# Qwiic_Spectral_Sensor-AS7265x.net
KiCad netlist of a schematic drawn in EAGLE
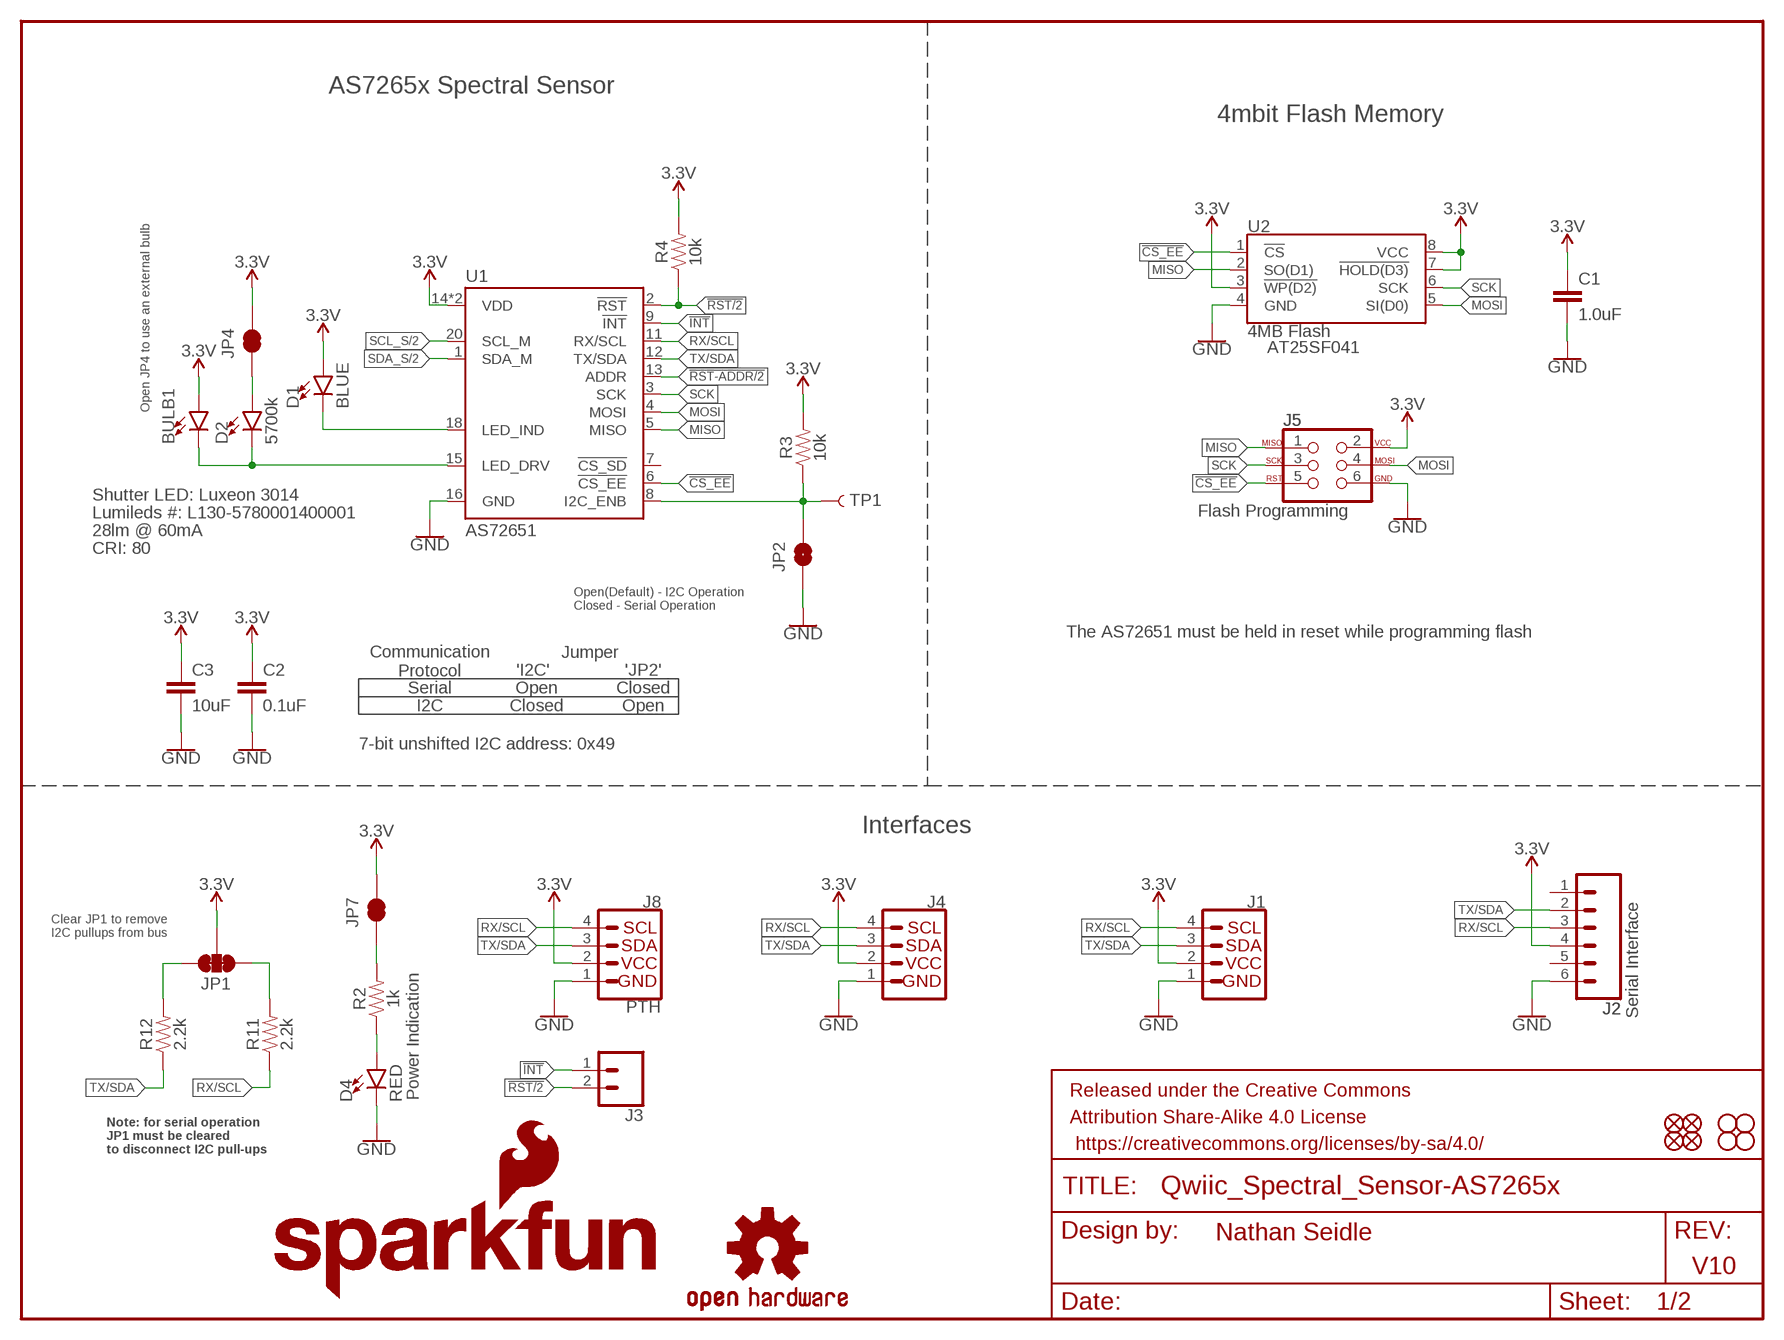
[diagram p0: schematic, sheet 1]
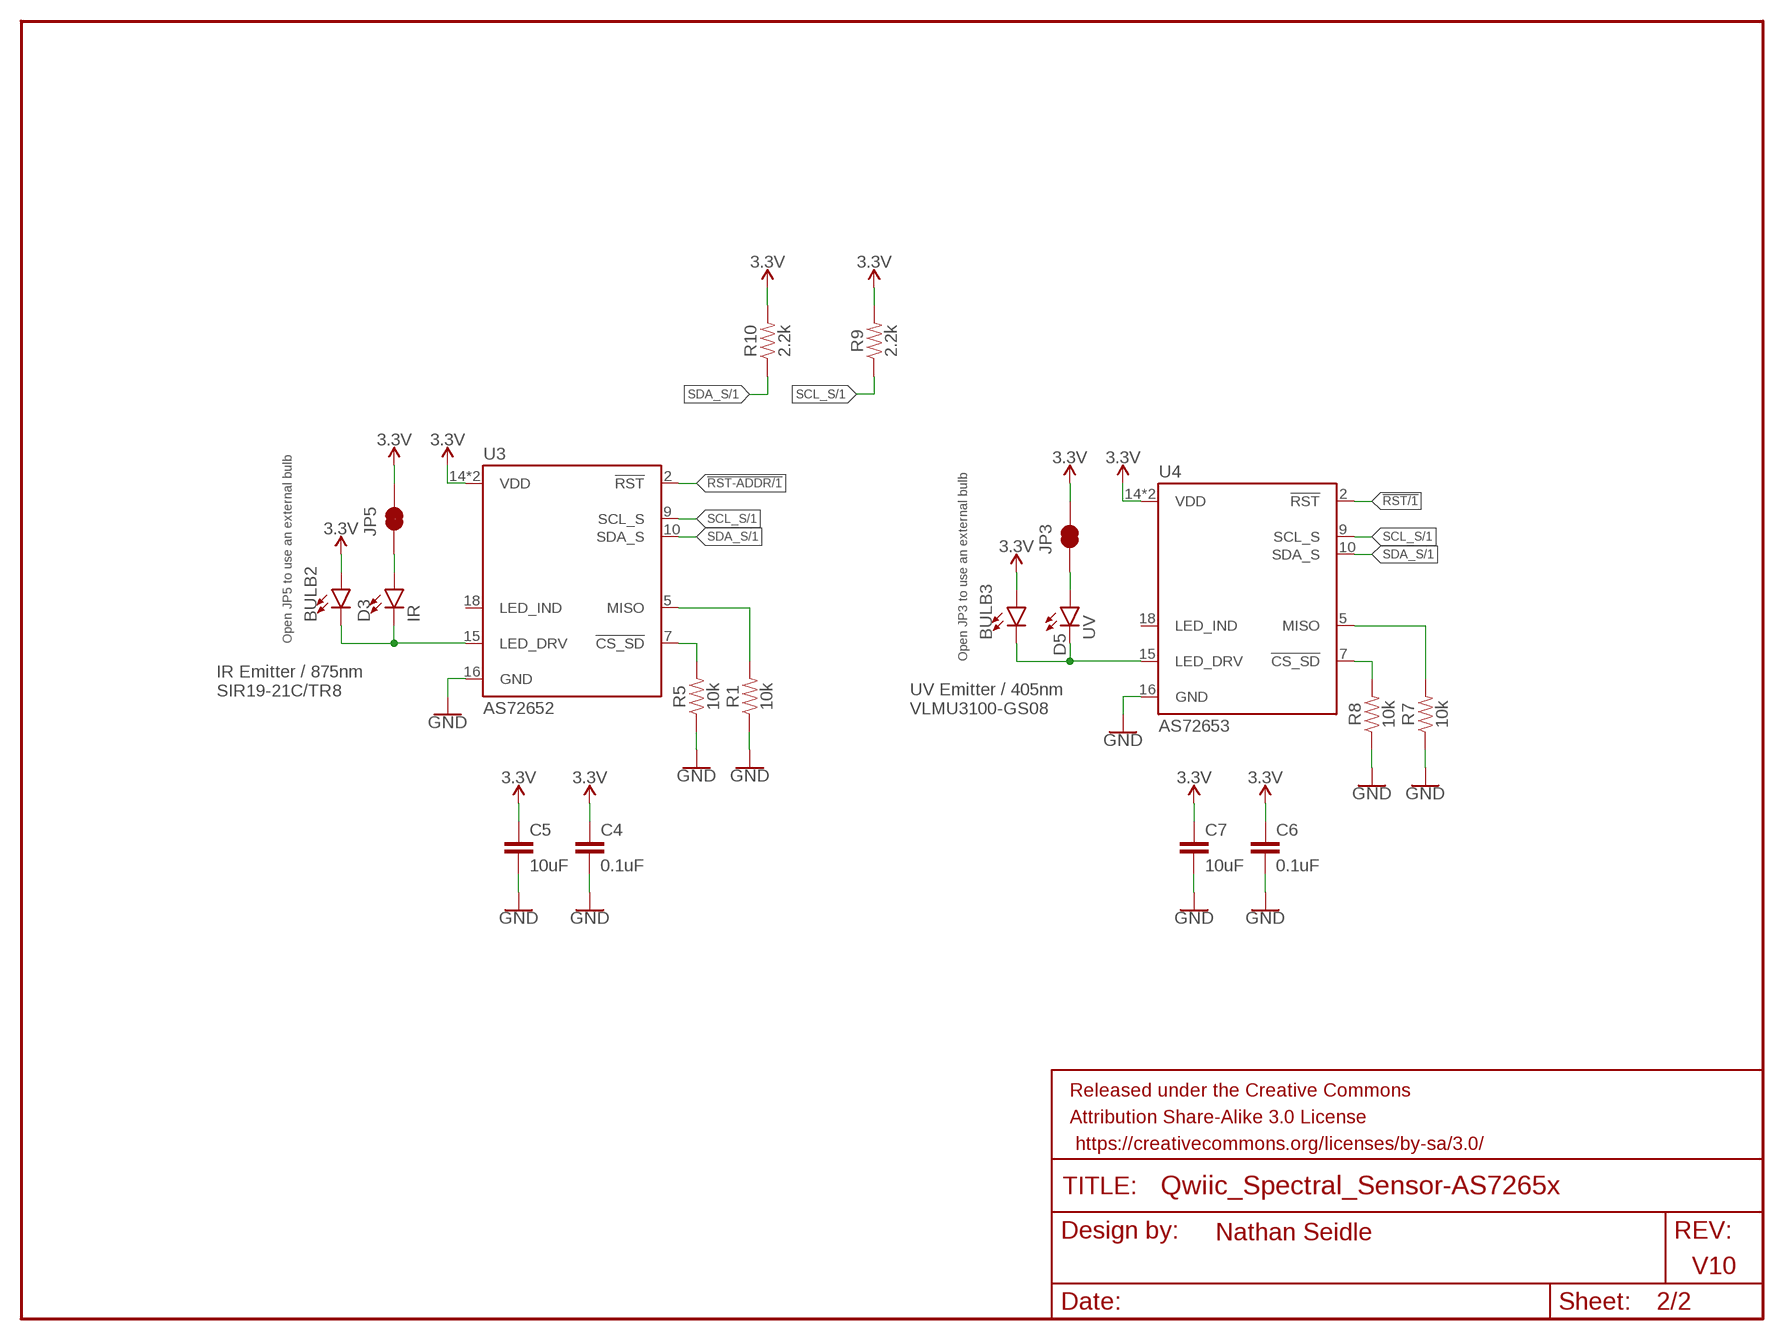
[diagram p1: schematic, sheet 2]

(export (version "E")
  (design (tool "Eeschema 10.0.6"))
  (components
    (comp (ref "BULB2")
      (value "LEDNS")
      (footprint "eagle-import:LED_5MM_NOSILK")
      (libsource (lib "eagle-import") (part "LEDNS"))
    )
    (comp (ref "BULB3")
      (value "LEDNS")
      (footprint "eagle-import:LED_5MM_NOSILK")
      (libsource (lib "eagle-import") (part "LEDNS"))
    )
    (comp (ref "C4")
      (value "0.1uF")
      (footprint "eagle-import:0603")
      (libsource (lib "eagle-import") (part "0.1UF-0603-25V-(+80/-20%)"))
    )
    (comp (ref "C5")
      (value "10uF")
      (footprint "eagle-import:0603")
      (libsource (lib "eagle-import") (part "10UF-0603-6.3V-20%"))
    )
    (comp (ref "C6")
      (value "0.1uF")
      (footprint "eagle-import:0603")
      (libsource (lib "eagle-import") (part "0.1UF-0603-25V-(+80/-20%)"))
    )
    (comp (ref "C7")
      (value "10uF")
      (footprint "eagle-import:0603")
      (libsource (lib "eagle-import") (part "10UF-0603-6.3V-20%"))
    )
    (comp (ref "D3")
      (value "IR")
      (footprint "eagle-import:LED-0603")
      (libsource (lib "eagle-import") (part "LED-IR0603"))
    )
    (comp (ref "D5")
      (value "UV")
      (footprint "eagle-import:PLCC-2")
      (libsource (lib "eagle-import") (part "LED-UVPLCC"))
    )
    (comp (ref "FRAME3")
      (value "FRAME-LETTER")
      (footprint "eagle-import:CREATIVE_COMMONS")
      (libsource (lib "eagle-import") (part "SparkFun-Retired_FRAME-LETTER"))
    )
    (comp (ref "JP3")
      (value "JUMPER-SMT_2_NC_TRACE_NO-SILK")
      (footprint "eagle-import:SMT-JUMPER_2_NC_TRACE_NO-SILK")
      (libsource (lib "eagle-import") (part "JUMPER-SMT_2_NC_TRACE_NO-SILK"))
    )
    (comp (ref "JP5")
      (value "JUMPER-SMT_2_NC_TRACE_NO-SILK")
      (footprint "eagle-import:SMT-JUMPER_2_NC_TRACE_NO-SILK")
      (libsource (lib "eagle-import") (part "JUMPER-SMT_2_NC_TRACE_NO-SILK"))
    )
    (comp (ref "R1")
      (value "10k")
      (footprint "eagle-import:0603")
      (libsource (lib "eagle-import") (part "10KOHM-0603-1/10W-1%"))
    )
    (comp (ref "R5")
      (value "10k")
      (footprint "eagle-import:0603")
      (libsource (lib "eagle-import") (part "10KOHM-0603-1/10W-1%"))
    )
    (comp (ref "R7")
      (value "10k")
      (footprint "eagle-import:0603")
      (libsource (lib "eagle-import") (part "10KOHM-0603-1/10W-1%"))
    )
    (comp (ref "R8")
      (value "10k")
      (footprint "eagle-import:0603")
      (libsource (lib "eagle-import") (part "10KOHM-0603-1/10W-1%"))
    )
    (comp (ref "R9")
      (value "2.2k")
      (footprint "eagle-import:0603")
      (libsource (lib "eagle-import") (part "2.2KOHM-0603-1/10W-1%"))
    )
    (comp (ref "R10")
      (value "2.2k")
      (footprint "eagle-import:0603")
      (libsource (lib "eagle-import") (part "2.2KOHM-0603-1/10W-1%"))
    )
    (comp (ref "U3")
      (value "AS72652")
      (footprint "eagle-import:LGA20")
      (libsource (lib "eagle-import") (part "AS72652"))
    )
    (comp (ref "U4")
      (value "AS72653")
      (footprint "eagle-import:LGA20")
      (libsource (lib "eagle-import") (part "AS72653"))
    )
    (comp (ref "BULB1")
      (value "LEDNS")
      (footprint "eagle-import:LED_5MM_NOSILK")
      (libsource (lib "eagle-import") (part "LEDNS"))
    )
    (comp (ref "C1")
      (value "1.0uF")
      (footprint "eagle-import:0603")
      (libsource (lib "eagle-import") (part "1.0UF-0603-16V-10%"))
    )
    (comp (ref "C2")
      (value "0.1uF")
      (footprint "eagle-import:0603")
      (libsource (lib "eagle-import") (part "0.1UF-0603-25V-(+80/-20%)"))
    )
    (comp (ref "C3")
      (value "10uF")
      (footprint "eagle-import:0603")
      (libsource (lib "eagle-import") (part "10UF-0603-6.3V-20%"))
    )
    (comp (ref "D1")
      (value "BLUE")
      (footprint "eagle-import:LED-0603")
      (libsource (lib "eagle-import") (part "LED-BLUE0603"))
    )
    (comp (ref "D2")
      (value "5700k")
      (footprint "eagle-import:SUPER_BRIGHT_SMD_LED_3014")
      (libsource (lib "eagle-import") (part "LED-WHITE3014"))
    )
    (comp (ref "D4")
      (value "RED")
      (footprint "eagle-import:LED-0603")
      (libsource (lib "eagle-import") (part "LED-RED0603"))
    )
    (comp (ref "FD1")
      (value "FIDUCIAL1X2")
      (footprint "eagle-import:FIDUCIAL-1X2")
      (libsource (lib "eagle-import") (part "FIDUCIAL1X2"))
    )
    (comp (ref "FD2")
      (value "FIDUCIAL1X2")
      (footprint "eagle-import:FIDUCIAL-1X2")
      (libsource (lib "eagle-import") (part "FIDUCIAL1X2"))
    )
    (comp (ref "FD3")
      (value "FIDUCIAL1X2")
      (footprint "eagle-import:FIDUCIAL-1X2")
      (libsource (lib "eagle-import") (part "FIDUCIAL1X2"))
    )
    (comp (ref "FD4")
      (value "FIDUCIAL1X2")
      (footprint "eagle-import:FIDUCIAL-1X2")
      (libsource (lib "eagle-import") (part "FIDUCIAL1X2"))
    )
    (comp (ref "FRAME1")
      (value "FRAME-LETTER")
      (footprint "eagle-import:CREATIVE_COMMONS")
      (libsource (lib "eagle-import") (part "FRAME-LETTER"))
    )
    (comp (ref "H1")
      (value "STAND-OFF")
      (footprint "eagle-import:STAND-OFF")
      (libsource (lib "eagle-import") (part "STAND-OFF"))
    )
    (comp (ref "H2")
      (value "STAND-OFF")
      (footprint "eagle-import:STAND-OFF")
      (libsource (lib "eagle-import") (part "STAND-OFF"))
    )
    (comp (ref "H3")
      (value "STAND-OFF")
      (footprint "eagle-import:STAND-OFF")
      (libsource (lib "eagle-import") (part "STAND-OFF"))
    )
    (comp (ref "H4")
      (value "STAND-OFF")
      (footprint "eagle-import:STAND-OFF")
      (libsource (lib "eagle-import") (part "STAND-OFF"))
    )
    (comp (ref "J1")
      (value "QWIIC_CONNECTORJS-1MM")
      (footprint "eagle-import:1X04_1MM_RA")
      (libsource (lib "eagle-import") (part "QWIIC_CONNECTORJS-1MM"))
    )
    (comp (ref "J2")
      (value "Serial Interface")
      (footprint "eagle-import:1X06_NO_SILK")
      (libsource (lib "eagle-import") (part "CONN_06NO_SILK_FEMALE_PTH"))
    )
    (comp (ref "J3")
      (value "CONN_021X02_NO_SILK")
      (footprint "eagle-import:1X02_NO_SILK")
      (libsource (lib "eagle-import") (part "CONN_021X02_NO_SILK"))
    )
    (comp (ref "J4")
      (value "QWIIC_CONNECTORJS-1MM")
      (footprint "eagle-import:1X04_1MM_RA")
      (libsource (lib "eagle-import") (part "QWIIC_CONNECTORJS-1MM"))
    )
    (comp (ref "J5")
      (value "Flash Programming")
      (footprint "eagle-import:2X3_TEST_POINTS")
      (libsource (lib "eagle-import") (part "AVR_SPI_PROG_3X2TESTPOINTS"))
    )
    (comp (ref "J8")
      (value "PTH")
      (footprint "eagle-import:1X04_NO_SILK")
      (libsource (lib "eagle-import") (part "I2C_STANDARD_NO_SILK"))
    )
    (comp (ref "JP1")
      (value "JUMPER-SMT_3_2-NC_TRACE_SILK")
      (footprint "eagle-import:SMT-JUMPER_3_2-NC_TRACE_SILK")
      (libsource (lib "eagle-import") (part "JUMPER-SMT_3_2-NC_TRACE_SILK"))
    )
    (comp (ref "JP2")
      (value "JUMPER-SMT_2_NO_SILK")
      (footprint "eagle-import:SMT-JUMPER_2_NO_SILK")
      (libsource (lib "eagle-import") (part "JUMPER-SMT_2_NO_SILK"))
    )
    (comp (ref "JP4")
      (value "JUMPER-SMT_2_NC_TRACE_NO-SILK")
      (footprint "eagle-import:SMT-JUMPER_2_NC_TRACE_NO-SILK")
      (libsource (lib "eagle-import") (part "JUMPER-SMT_2_NC_TRACE_NO-SILK"))
    )
    (comp (ref "JP7")
      (value "JUMPER-SMT_2_NC_TRACE_NO-SILK")
      (footprint "eagle-import:SMT-JUMPER_2_NC_TRACE_NO-SILK")
      (libsource (lib "eagle-import") (part "JUMPER-SMT_2_NC_TRACE_NO-SILK"))
    )
    (comp (ref "LOGO1")
      (value "SFE_LOGO_NAME_FLAME.1_INCH")
      (footprint "eagle-import:SFE_LOGO_NAME_FLAME_.1")
      (libsource (lib "eagle-import") (part "SFE_LOGO_NAME_FLAME.1_INCH"))
    )
    (comp (ref "LOGO4")
      (value "OSHW-LOGOS")
      (footprint "eagle-import:OSHW-LOGO-S")
      (libsource (lib "eagle-import") (part "OSHW-LOGOS"))
    )
    (comp (ref "R2")
      (value "1k")
      (footprint "eagle-import:0603")
      (libsource (lib "eagle-import") (part "1KOHM-0603-1/10W-1%"))
    )
    (comp (ref "R3")
      (value "10k")
      (footprint "eagle-import:0603")
      (libsource (lib "eagle-import") (part "10KOHM-0603-1/10W-1%"))
    )
    (comp (ref "R4")
      (value "10k")
      (footprint "eagle-import:0603")
      (libsource (lib "eagle-import") (part "10KOHM-0603-1/10W-1%"))
    )
    (comp (ref "R11")
      (value "2.2k")
      (footprint "eagle-import:0603")
      (libsource (lib "eagle-import") (part "2.2KOHM-0603-1/10W-1%"))
    )
    (comp (ref "R12")
      (value "2.2k")
      (footprint "eagle-import:0603")
      (libsource (lib "eagle-import") (part "2.2KOHM-0603-1/10W-1%"))
    )
    (comp (ref "TP1")
      (value "TEST-POINT3")
      (footprint "eagle-import:PAD.03X.03")
      (libsource (lib "eagle-import") (part "TEST-POINT3"))
    )
    (comp (ref "U1")
      (value "AS72651")
      (footprint "eagle-import:LGA20")
      (libsource (lib "eagle-import") (part "AS72651"))
    )
    (comp (ref "U2")
      (value "4MB Flash")
      (footprint "eagle-import:SO08")
      (libsource (lib "eagle-import") (part "AT25SF041"))
    )
  )
  (nets
    (net (code "1") (name "3.3V") (class "Default")
      (node (ref "BULB1") (pin "A") (pinfunction "A_A") (pintype "passive"))
      (node (ref "BULB2") (pin "A") (pinfunction "A_A") (pintype "passive"))
      (node (ref "BULB3") (pin "A") (pinfunction "A_A") (pintype "passive"))
      (node (ref "C1") (pin "1") (pinfunction "1_1") (pintype "passive"))
      (node (ref "C2") (pin "1") (pinfunction "1_1") (pintype "passive"))
      (node (ref "C3") (pin "1") (pinfunction "1_1") (pintype "passive"))
      (node (ref "C4") (pin "1") (pinfunction "1_1") (pintype "passive"))
      (node (ref "C5") (pin "1") (pinfunction "1_1") (pintype "passive"))
      (node (ref "C6") (pin "1") (pinfunction "1_1") (pintype "passive"))
      (node (ref "C7") (pin "1") (pinfunction "1_1") (pintype "passive"))
      (node (ref "D1") (pin "A") (pinfunction "A_A") (pintype "passive"))
      (node (ref "J1") (pin "2") (pinfunction "2_2") (pintype "power_in"))
      (node (ref "J2") (pin "4") (pinfunction "4_4") (pintype "passive"))
      (node (ref "J4") (pin "2") (pinfunction "2_2") (pintype "power_in"))
      (node (ref "J5") (pin "2") (pinfunction "2_2") (pintype "passive"))
      (node (ref "J8") (pin "2") (pinfunction "2_2") (pintype "power_in"))
      (node (ref "JP1") (pin "2") (pinfunction "2_2") (pintype "passive"))
      (node (ref "JP3") (pin "2") (pinfunction "2_2") (pintype "passive"))
      (node (ref "JP4") (pin "2") (pinfunction "2_2") (pintype "passive"))
      (node (ref "JP5") (pin "2") (pinfunction "2_2") (pintype "passive"))
      (node (ref "JP7") (pin "2") (pinfunction "2_2") (pintype "passive"))
      (node (ref "R10") (pin "2") (pinfunction "2_2") (pintype "passive"))
      (node (ref "R3") (pin "2") (pinfunction "2_2") (pintype "passive"))
      (node (ref "R4") (pin "2") (pinfunction "2_2") (pintype "passive"))
      (node (ref "R9") (pin "2") (pinfunction "2_2") (pintype "passive"))
      (node (ref "U1") (pin "14") (pinfunction "VDD_14") (pintype "bidirectional"))
      (node (ref "U1") (pin "17") (pinfunction "VDD_17") (pintype "bidirectional"))
      (node (ref "U2") (pin "3") (pinfunction "~{WP(D2})_3") (pintype "bidirectional"))
      (node (ref "U2") (pin "7") (pinfunction "~{HOLD(D3})_7") (pintype "bidirectional"))
      (node (ref "U2") (pin "8") (pinfunction "VCC_8") (pintype "bidirectional"))
      (node (ref "U3") (pin "14") (pinfunction "VDD_14") (pintype "bidirectional"))
      (node (ref "U3") (pin "17") (pinfunction "VDD_17") (pintype "bidirectional"))
      (node (ref "U4") (pin "14") (pinfunction "VDD_14") (pintype "bidirectional"))
      (node (ref "U4") (pin "17") (pinfunction "VDD_17") (pintype "bidirectional"))
    )
    (net (code "2") (name "GND") (class "Default")
      (node (ref "C1") (pin "2") (pinfunction "2_2") (pintype "passive"))
      (node (ref "C2") (pin "2") (pinfunction "2_2") (pintype "passive"))
      (node (ref "C3") (pin "2") (pinfunction "2_2") (pintype "passive"))
      (node (ref "C4") (pin "2") (pinfunction "2_2") (pintype "passive"))
      (node (ref "C5") (pin "2") (pinfunction "2_2") (pintype "passive"))
      (node (ref "C6") (pin "2") (pinfunction "2_2") (pintype "passive"))
      (node (ref "C7") (pin "2") (pinfunction "2_2") (pintype "passive"))
      (node (ref "D4") (pin "C") (pinfunction "C_C") (pintype "passive"))
      (node (ref "J1") (pin "1") (pinfunction "1_1") (pintype "power_in"))
      (node (ref "J2") (pin "6") (pinfunction "6_6") (pintype "passive"))
      (node (ref "J4") (pin "1") (pinfunction "1_1") (pintype "power_in"))
      (node (ref "J5") (pin "6") (pinfunction "6_6") (pintype "passive"))
      (node (ref "J8") (pin "1") (pinfunction "1_1") (pintype "power_in"))
      (node (ref "JP2") (pin "1") (pinfunction "1_1") (pintype "passive"))
      (node (ref "R1") (pin "1") (pinfunction "1_1") (pintype "passive"))
      (node (ref "R5") (pin "1") (pinfunction "1_1") (pintype "passive"))
      (node (ref "R7") (pin "1") (pinfunction "1_1") (pintype "passive"))
      (node (ref "R8") (pin "1") (pinfunction "1_1") (pintype "passive"))
      (node (ref "U1") (pin "16") (pinfunction "GND_16") (pintype "bidirectional"))
      (node (ref "U2") (pin "4") (pinfunction "GND_4") (pintype "bidirectional"))
      (node (ref "U3") (pin "16") (pinfunction "GND_16") (pintype "bidirectional"))
      (node (ref "U4") (pin "16") (pinfunction "GND_16") (pintype "bidirectional"))
    )
    (net (code "3") (name "MISO") (class "Default")
      (node (ref "J5") (pin "1") (pinfunction "1_1") (pintype "passive"))
      (node (ref "U1") (pin "5") (pinfunction "MISO_5") (pintype "bidirectional"))
      (node (ref "U2") (pin "2") (pinfunction "SO(D1)_2") (pintype "bidirectional"))
    )
    (net (code "4") (name "MOSI") (class "Default")
      (node (ref "J5") (pin "4") (pinfunction "4_4") (pintype "passive"))
      (node (ref "U1") (pin "4") (pinfunction "MOSI_4") (pintype "bidirectional"))
      (node (ref "U2") (pin "5") (pinfunction "SI(D0)_5") (pintype "bidirectional"))
    )
    (net (code "5") (name "Net-(BULB1-C)") (class "Default")
      (node (ref "BULB1") (pin "K") (pinfunction "C_K") (pintype "passive"))
      (node (ref "D2") (pin "C") (pinfunction "C_C") (pintype "passive"))
      (node (ref "U1") (pin "15") (pinfunction "LED_DRV_15") (pintype "bidirectional"))
    )
    (net (code "6") (name "Net-(BULB2-C)") (class "Default")
      (node (ref "BULB2") (pin "K") (pinfunction "C_K") (pintype "passive"))
      (node (ref "D3") (pin "C") (pinfunction "C_C") (pintype "passive"))
      (node (ref "U3") (pin "15") (pinfunction "LED_DRV_15") (pintype "bidirectional"))
    )
    (net (code "7") (name "Net-(BULB3-C)") (class "Default")
      (node (ref "BULB3") (pin "K") (pinfunction "C_K") (pintype "passive"))
      (node (ref "D5") (pin "C") (pinfunction "C_C") (pintype "passive"))
      (node (ref "U4") (pin "15") (pinfunction "LED_DRV_15") (pintype "bidirectional"))
    )
    (net (code "8") (name "Net-(D2-PadA)") (class "Default")
      (node (ref "D2") (pin "A") (pinfunction "A_A") (pintype "passive"))
      (node (ref "JP4") (pin "1") (pinfunction "1_1") (pintype "passive"))
    )
    (net (code "9") (name "Net-(D3-PadA)") (class "Default")
      (node (ref "D3") (pin "A") (pinfunction "A_A") (pintype "passive"))
      (node (ref "JP5") (pin "1") (pinfunction "1_1") (pintype "passive"))
    )
    (net (code "10") (name "Net-(D4-PadA)") (class "Default")
      (node (ref "D4") (pin "A") (pinfunction "A_A") (pintype "passive"))
      (node (ref "R2") (pin "1") (pinfunction "1_1") (pintype "passive"))
    )
    (net (code "11") (name "Net-(D5-PadA)") (class "Default")
      (node (ref "D5") (pin "A") (pinfunction "A_A") (pintype "passive"))
      (node (ref "JP3") (pin "1") (pinfunction "1_1") (pintype "passive"))
    )
    (net (code "12") (name "Net-(JP1-Pad1)") (class "Default")
      (node (ref "JP1") (pin "1") (pinfunction "1_1") (pintype "passive"))
      (node (ref "R11") (pin "2") (pinfunction "2_2") (pintype "passive"))
    )
    (net (code "13") (name "Net-(JP1-Pad3)") (class "Default")
      (node (ref "JP1") (pin "3") (pinfunction "3_3") (pintype "passive"))
      (node (ref "R12") (pin "2") (pinfunction "2_2") (pintype "passive"))
    )
    (net (code "14") (name "Net-(JP7-Pad1)") (class "Default")
      (node (ref "JP7") (pin "1") (pinfunction "1_1") (pintype "passive"))
      (node (ref "R2") (pin "2") (pinfunction "2_2") (pintype "passive"))
    )
    (net (code "15") (name "Net-(TP1-1)") (class "Default")
      (node (ref "JP2") (pin "2") (pinfunction "2_2") (pintype "passive"))
      (node (ref "R3") (pin "1") (pinfunction "1_1") (pintype "passive"))
      (node (ref "TP1") (pin "P$1") (pinfunction "1_P$1") (pintype "bidirectional"))
      (node (ref "U1") (pin "8") (pinfunction "I2C_ENB_8") (pintype "bidirectional"))
    )
    (net (code "16") (name "Net-(U1-LED_IND)") (class "Default")
      (node (ref "D1") (pin "C") (pinfunction "C_C") (pintype "passive"))
      (node (ref "U1") (pin "18") (pinfunction "LED_IND_18") (pintype "bidirectional"))
    )
    (net (code "17") (name "Net-(U3-MISO)") (class "Default")
      (node (ref "R1") (pin "2") (pinfunction "2_2") (pintype "passive"))
      (node (ref "U3") (pin "5") (pinfunction "MISO_5") (pintype "bidirectional"))
    )
    (net (code "18") (name "Net-(U3-~{CS_SD})") (class "Default")
      (node (ref "R5") (pin "2") (pinfunction "2_2") (pintype "passive"))
      (node (ref "U3") (pin "7") (pinfunction "~{CS_SD}_7") (pintype "bidirectional"))
    )
    (net (code "19") (name "Net-(U4-MISO)") (class "Default")
      (node (ref "R7") (pin "2") (pinfunction "2_2") (pintype "passive"))
      (node (ref "U4") (pin "5") (pinfunction "MISO_5") (pintype "bidirectional"))
    )
    (net (code "20") (name "Net-(U4-~{CS_SD})") (class "Default")
      (node (ref "R8") (pin "2") (pinfunction "2_2") (pintype "passive"))
      (node (ref "U4") (pin "7") (pinfunction "~{CS_SD}_7") (pintype "bidirectional"))
    )
    (net (code "21") (name "RX{slash}SCL") (class "Default")
      (node (ref "J1") (pin "4") (pinfunction "4_4") (pintype "passive"))
      (node (ref "J2") (pin "3") (pinfunction "3_3") (pintype "passive"))
      (node (ref "J4") (pin "4") (pinfunction "4_4") (pintype "passive"))
      (node (ref "J8") (pin "4") (pinfunction "4_4") (pintype "passive"))
      (node (ref "R11") (pin "1") (pinfunction "1_1") (pintype "passive"))
      (node (ref "U1") (pin "11") (pinfunction "RX/SCL_11") (pintype "bidirectional"))
    )
    (net (code "22") (name "SCK") (class "Default")
      (node (ref "J5") (pin "3") (pinfunction "3_3") (pintype "passive"))
      (node (ref "U1") (pin "3") (pinfunction "SCK_3") (pintype "bidirectional"))
      (node (ref "U2") (pin "6") (pinfunction "SCK_6") (pintype "bidirectional"))
    )
    (net (code "23") (name "SCL_S") (class "Default")
      (node (ref "R9") (pin "1") (pinfunction "1_1") (pintype "passive"))
      (node (ref "U1") (pin "20") (pinfunction "SCL_M_20") (pintype "bidirectional"))
      (node (ref "U3") (pin "9") (pinfunction "SCL_S_9") (pintype "bidirectional"))
      (node (ref "U4") (pin "9") (pinfunction "SCL_S_9") (pintype "bidirectional"))
    )
    (net (code "24") (name "SDA_S") (class "Default")
      (node (ref "R10") (pin "1") (pinfunction "1_1") (pintype "passive"))
      (node (ref "U1") (pin "1") (pinfunction "SDA_M_1") (pintype "bidirectional"))
      (node (ref "U3") (pin "10") (pinfunction "SDA_S_10") (pintype "bidirectional"))
      (node (ref "U4") (pin "10") (pinfunction "SDA_S_10") (pintype "bidirectional"))
    )
    (net (code "25") (name "TX{slash}SDA") (class "Default")
      (node (ref "J1") (pin "3") (pinfunction "3_3") (pintype "passive"))
      (node (ref "J2") (pin "2") (pinfunction "2_2") (pintype "passive"))
      (node (ref "J4") (pin "3") (pinfunction "3_3") (pintype "passive"))
      (node (ref "J8") (pin "3") (pinfunction "3_3") (pintype "passive"))
      (node (ref "R12") (pin "1") (pinfunction "1_1") (pintype "passive"))
      (node (ref "U1") (pin "12") (pinfunction "TX/SDA_12") (pintype "bidirectional"))
    )
    (net (code "26") (name "unconnected-(J2-Pad1)") (class "Default")
      (node (ref "J2") (pin "1") (pinfunction "1_1") (pintype "passive"))
    )
    (net (code "27") (name "unconnected-(J2-Pad5)") (class "Default")
      (node (ref "J2") (pin "5") (pinfunction "5_5") (pintype "passive"))
    )
    (net (code "28") (name "unconnected-(U1-~{CS_SD}-Pad7)") (class "Default")
      (node (ref "U1") (pin "7") (pinfunction "~{CS_SD}_7") (pintype "bidirectional"))
    )
    (net (code "29") (name "unconnected-(U3-LED_IND-Pad18)") (class "Default")
      (node (ref "U3") (pin "18") (pinfunction "LED_IND_18") (pintype "bidirectional"))
    )
    (net (code "30") (name "unconnected-(U4-LED_IND-Pad18)") (class "Default")
      (node (ref "U4") (pin "18") (pinfunction "LED_IND_18") (pintype "bidirectional"))
    )
    (net (code "31") (name "~{CS_EE}") (class "Default")
      (node (ref "J5") (pin "5") (pinfunction "5_5") (pintype "passive"))
      (node (ref "U1") (pin "6") (pinfunction "~{CS_EE}_6") (pintype "bidirectional"))
      (node (ref "U2") (pin "1") (pinfunction "~{CS}_1") (pintype "bidirectional"))
    )
    (net (code "32") (name "~{INT}") (class "Default")
      (node (ref "J3") (pin "1") (pinfunction "1_1") (pintype "passive"))
      (node (ref "U1") (pin "9") (pinfunction "~{INT}_9") (pintype "bidirectional"))
    )
    (net (code "33") (name "~{RST-ADDR}") (class "Default")
      (node (ref "U1") (pin "13") (pinfunction "ADDR_13") (pintype "bidirectional"))
      (node (ref "U3") (pin "2") (pinfunction "~{RST}_2") (pintype "bidirectional"))
    )
    (net (code "34") (name "~{RST}") (class "Default")
      (node (ref "J3") (pin "2") (pinfunction "2_2") (pintype "passive"))
      (node (ref "R4") (pin "1") (pinfunction "1_1") (pintype "passive"))
      (node (ref "U1") (pin "2") (pinfunction "~{RST}_2") (pintype "bidirectional"))
      (node (ref "U4") (pin "2") (pinfunction "~{RST}_2") (pintype "bidirectional"))
    )
  )
)
